# USB-C.net
KiCad netlist of a schematic drawn in Altium Designer
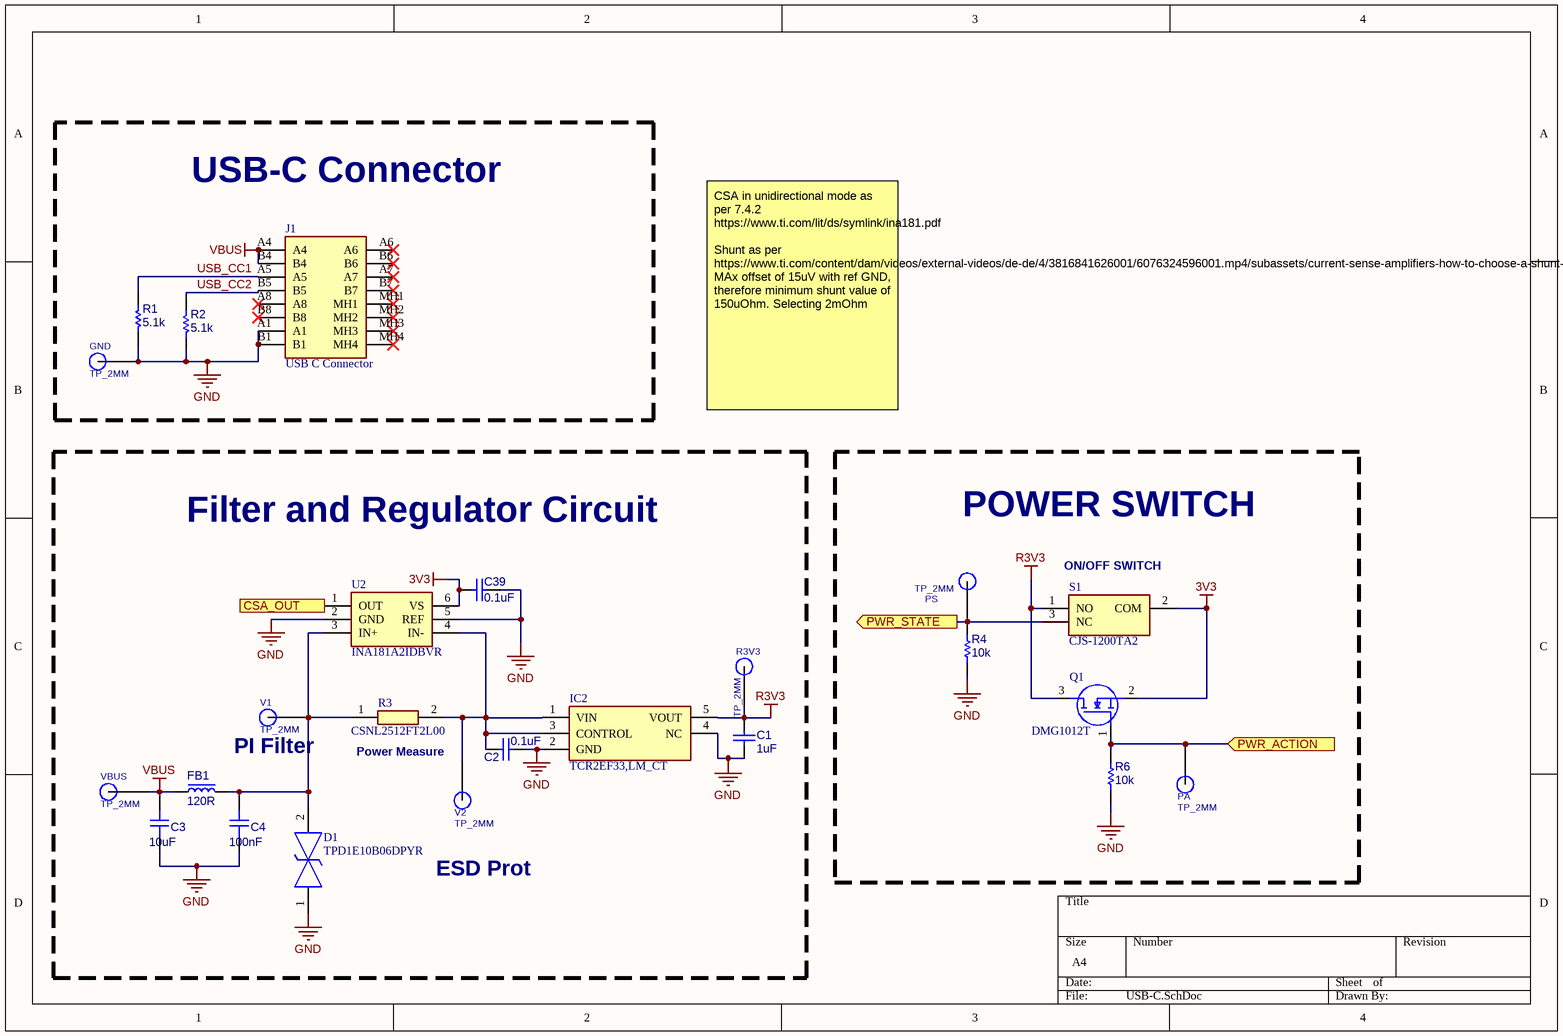
[diagram p0: USB-C.SchDoc]

(export (version "E")
  (design (tool "Eeschema 10.0.6"))
  (components
    (comp (ref "C1")
      (value "1uF")
      (footprint "C0603")
      (description "Capacitor, MLCC, 100nF, 6V3, X5R, 10%, 0603, T=0,8mm")
      (fields
        (field (name "MANUFACTURER PART NUMBER") "CC0603KRX5R5BB104")
        (field (name "MANUFACTURER") "YAGEO")
        (field (name "PROVIDED_BY") "SUBCO")
      )
      (libsource (lib "Perth Aerospace Student Team") (part "CMP-035-000015-1"))
    )
    (comp (ref "C2")
      (value "0.1uF")
      (footprint "C0603")
      (description "Capacitor, MLCC, 100nF, 6V3, X5R, 10%, 0603, T=0,8mm")
      (fields
        (field (name "MANUFACTURER PART NUMBER") "CC0603KRX5R5BB104")
        (field (name "MANUFACTURER") "YAGEO")
        (field (name "PROVIDED_BY") "SUBCO")
      )
      (libsource (lib "Perth Aerospace Student Team") (part "CMP-035-000015-1"))
    )
    (comp (ref "C3")
      (value "CAP_0603_16V")
      (footprint "CAP_0603")
      (description "Capacitor SMD 0603 16V")
      (fields (field (name "SOURCE") "Schematic-Lib-PhilsLab.SchLib"))
      (libsource (lib "Perth Aerospace Student Team") (part "CAP_EL_NP_5MM"))
    )
    (comp (ref "C4")
      (value "CAP_0603_16V")
      (footprint "CAP_0603")
      (description "Capacitor SMD 0603 16V")
      (fields (field (name "SOURCE") "Schematic-Lib-PhilsLab.SchLib"))
      (libsource (lib "Perth Aerospace Student Team") (part "CAP_EL_NP_5MM"))
    )
    (comp (ref "C39")
      (value "0.1uF")
      (footprint "C0603")
      (description "Capacitor, MLCC, 100nF, 6V3, X5R, 10%, 0603, T=0,8mm")
      (fields
        (field (name "MANUFACTURER PART NUMBER") "CC0603KRX5R5BB104")
        (field (name "MANUFACTURER") "YAGEO")
        (field (name "PROVIDED_BY") "SUBCO")
      )
      (libsource (lib "Perth Aerospace Student Team") (part "CMP-035-000015-1"))
    )
    (comp (ref "D1")
      (value "TPD1E10B06DPYR")
      (footprint "TPD1E10B06DPYR")
      (description "TVS Diode (Bi-directional)")
      (fields (field (name "MOUSER PART NUMBER") "595-TPD1E10B06DPYR"))
      (libsource (lib "C2S") (part "TPD1E10B06DPYR"))
    )
    (comp (ref "FB1")
      (value "120R")
      (footprint "FB_0603")
      (description "Ferrite Bead SMD 0603")
      (fields (field (name "SOURCE") "Schematic-Lib-PhilsLab.SchLib"))
      (libsource (lib "Perth Aerospace Student Team") (part "FB_0603"))
    )
    (comp (ref "GND") (value "TP_2MM") (footprint "TESTPOINT 2MM") (libsource (lib "C2S") (part "TP_2MM")))
    (comp (ref "IC2")
      (value "TCR2EF33,LM_CT")
      (footprint "C2Sv0.1:SOT-25")
      (description "Integrated Circuit")
      (fields
        (field (name "MANUFACTURER_PART_NUMBER") "TCR2EF33,LM(CT")
        (field (name "MOUSER PART NUMBER") "757-TCR2EF33LMCT")
      )
      (libsource (lib "C2Sv0.1") (part "TCR2EF33,LM_CT"))
    )
    (comp (ref "J1")
      (value "USB C Connector")
      (footprint "UJ20CHGMSMT2P16TR")
      (description "UJ20-C-H-G-MSMT-2-P16-TR Connector")
      (fields
        (field (name "MOUSER PART NUMBER") "179-UJ20CHGMSMT2P16T")
        (field (name "MANUFACTURER_PART_NUMBER") "UJ20-C-H-G-MSMT-2-P16-TR")
        (field (name "AUTHOR") "Raphael Ho")
      )
      (libsource (lib "Perth Aerospace Student Team") (part "UJ20-C-H-G-MSMT-2-P16-TR"))
    )
    (comp (ref "PA") (value "TP_2MM") (footprint "TESTPOINT 2MM") (libsource (lib "C2S") (part "TP_2MM")))
    (comp (ref "PS") (value "TP_2MM") (footprint "TESTPOINT 2MM") (libsource (lib "C2S") (part "TP_2MM")))
    (comp (ref "Q1")
      (value "DMG1012T")
      (footprint "SOT50P160X90-3N")
      (description "MOSFET (N-Channel)")
      (libsource (lib "C2S") (part "DMG1012T"))
    )
    (comp (ref "R1")
      (value "5.1k")
      (footprint "RESC1608X55X25ML10T15-1")
      (description "Chip Resistor, 10k Ohm, 0.1 W, -55 to 155 degC, 0603 (1608 Metric)")
      (fields
        (field (name "POWER") "100mW")
        (field (name "TOLERANCE") "1%")
        (field (name "CREATED BY") "Micah Randall")
      )
      (libsource (lib "Perth Aerospace Student Team") (part "CMP-009-00006-5"))
    )
    (comp (ref "R2")
      (value "5.1k")
      (footprint "RESC1608X55X25ML10T15-1")
      (description "Chip Resistor, 10k Ohm, 0.1 W, -55 to 155 degC, 0603 (1608 Metric)")
      (fields
        (field (name "POWER") "100mW")
        (field (name "TOLERANCE") "1%")
        (field (name "CREATED BY") "Micah Randall")
      )
      (libsource (lib "Perth Aerospace Student Team") (part "CMP-009-00006-5"))
    )
    (comp (ref "R3")
      (value "CSNL2512FT2L00")
      (footprint "C2Sv0.1:RESC6432X145N")
      (description "Resistor")
      (libsource (lib "*") (part "CSNL2512FT2L00"))
    )
    (comp (ref "R3V3") (value "TP_2MM") (footprint "TESTPOINT 2MM") (libsource (lib "C2S") (part "TP_2MM")))
    (comp (ref "R4")
      (value "10k")
      (footprint "RESC1608X55X25ML10T15-1")
      (description "Chip Resistor, 10k Ohm, 0.1 W, -55 to 155 degC, 0603 (1608 Metric)")
      (fields
        (field (name "POWER") "100mW")
        (field (name "TOLERANCE") "1%")
        (field (name "CREATED BY") "Micah Randall")
      )
      (libsource (lib "Perth Aerospace Student Team") (part "CMP-009-00006-5"))
    )
    (comp (ref "R6")
      (value "10k")
      (footprint "RESC1608X55X25ML10T15-1")
      (description "Chip Resistor, 10k Ohm, 0.1 W, -55 to 155 degC, 0603 (1608 Metric)")
      (fields
        (field (name "POWER") "100mW")
        (field (name "TOLERANCE") "1%")
        (field (name "CREATED BY") "Micah Randall")
      )
      (libsource (lib "Perth Aerospace Student Team") (part "CMP-009-00006-5"))
    )
    (comp (ref "S1")
      (value "CJS-1200TA2")
      (footprint "CJS1200TA2")
      (description "Switch")
      (fields (field (name "MOUSER PART NUMBER") "229-CJS-1200TA2"))
      (libsource (lib "C2S") (part "CJS-1200TA2"))
    )
    (comp (ref "U2")
      (value "INA181A2IDBVR")
      (footprint "C2Sv0.1:SOT95P280X145-6N")
      (description "Undefined or Miscellaneous")
      (fields (field (name "MOUSER PART NUMBER") "595-INA181A2IDBVR"))
      (libsource (lib "*") (part "INA181A2IDBVR"))
    )
    (comp (ref "V1") (value "TP_2MM") (footprint "TESTPOINT 2MM") (libsource (lib "C2S") (part "TP_2MM")))
    (comp (ref "V2") (value "TP_2MM") (footprint "TESTPOINT 2MM") (libsource (lib "C2S") (part "TP_2MM")))
    (comp (ref "VBUS") (value "TP_2MM") (footprint "TESTPOINT 2MM") (libsource (lib "C2S") (part "TP_2MM")))
  )
  (nets
    (net (code "1") (name "/CSA_OUT") (class "Default")
      (node (ref "U2") (pin "1") (pinfunction "OUT_1") (pintype "passive"))
    )
    (net (code "2") (name "/PWR_ACTION") (class "Default")
      (node (ref "PA") (pin "TP") (pinfunction "TP_2MM_TP") (pintype "passive"))
      (node (ref "Q1") (pin "1") (pinfunction "G_1") (pintype "passive"))
      (node (ref "R6") (pin "1") (pinfunction "1_1") (pintype "passive"))
    )
    (net (code "3") (name "/PWR_STATE") (class "Default")
      (node (ref "PS") (pin "TP") (pinfunction "TP_2MM_TP") (pintype "passive"))
      (node (ref "R4") (pin "1") (pinfunction "1_1") (pintype "passive"))
      (node (ref "S1") (pin "3") (pinfunction "NC_3") (pintype "passive"))
    )
    (net (code "4") (name "/USB_CC1") (class "Default")
      (node (ref "J1") (pin "A5") (pinfunction "A5_A5") (pintype "passive"))
      (node (ref "R1") (pin "1") (pinfunction "1_1") (pintype "passive"))
    )
    (net (code "5") (name "/USB_CC2") (class "Default")
      (node (ref "J1") (pin "B5") (pinfunction "B5_B5") (pintype "passive"))
      (node (ref "R2") (pin "1") (pinfunction "1_1") (pintype "passive"))
    )
    (net (code "6") (name "3V3") (class "Default")
      (node (ref "C39") (pin "1") (pinfunction "1_1") (pintype "passive"))
      (node (ref "Q1") (pin "2") (pinfunction "S_2") (pintype "passive"))
      (node (ref "S1") (pin "2") (pinfunction "COM_2") (pintype "passive"))
      (node (ref "U2") (pin "6") (pinfunction "VS_6") (pintype "passive"))
    )
    (net (code "7") (name "GND") (class "Default")
      (node (ref "C1") (pin "2") (pinfunction "2_2") (pintype "passive"))
      (node (ref "C2") (pin "1") (pinfunction "1_1") (pintype "passive"))
      (node (ref "C3") (pin "1") (pinfunction "1_1") (pintype "passive"))
      (node (ref "C39") (pin "2") (pinfunction "2_2") (pintype "passive"))
      (node (ref "C4") (pin "1") (pinfunction "1_1") (pintype "passive"))
      (node (ref "D1") (pin "1") (pinfunction "1_1") (pintype "passive"))
      (node (ref "GND") (pin "TP") (pinfunction "TP_2MM_TP") (pintype "passive"))
      (node (ref "IC2") (pin "2") (pinfunction "GND_2") (pintype "passive"))
      (node (ref "IC2") (pin "4") (pinfunction "NC_4") (pintype "passive"))
      (node (ref "J1") (pin "A1") (pinfunction "A1_A1") (pintype "passive"))
      (node (ref "J1") (pin "B1") (pinfunction "B1_B1") (pintype "passive"))
      (node (ref "R1") (pin "2") (pinfunction "2_2") (pintype "passive"))
      (node (ref "R2") (pin "2") (pinfunction "2_2") (pintype "passive"))
      (node (ref "R4") (pin "2") (pinfunction "2_2") (pintype "passive"))
      (node (ref "R6") (pin "2") (pinfunction "2_2") (pintype "passive"))
      (node (ref "U2") (pin "2") (pinfunction "GND_2") (pintype "passive"))
      (node (ref "U2") (pin "5") (pinfunction "REF_5") (pintype "passive"))
    )
    (net (code "8") (name "Net-(IC2-CONTROL)") (class "Default")
      (node (ref "C2") (pin "2") (pinfunction "2_2") (pintype "passive"))
      (node (ref "IC2") (pin "1") (pinfunction "VIN_1") (pintype "passive"))
      (node (ref "IC2") (pin "3") (pinfunction "CONTROL_3") (pintype "passive"))
      (node (ref "R3") (pin "2") (pinfunction "2_2") (pintype "passive"))
      (node (ref "U2") (pin "4") (pinfunction "IN-_4") (pintype "passive"))
      (node (ref "V2") (pin "TP") (pinfunction "TP_2MM_TP") (pintype "passive"))
    )
    (net (code "9") (name "Net-(U2-IN+)") (class "Default")
      (node (ref "C4") (pin "2") (pinfunction "2_2") (pintype "passive"))
      (node (ref "D1") (pin "2") (pinfunction "2_2") (pintype "passive"))
      (node (ref "FB1") (pin "1") (pinfunction "1_1") (pintype "passive"))
      (node (ref "R3") (pin "1") (pinfunction "1_1") (pintype "passive"))
      (node (ref "U2") (pin "3") (pinfunction "IN+_3") (pintype "passive"))
      (node (ref "V1") (pin "TP") (pinfunction "TP_2MM_TP") (pintype "passive"))
    )
    (net (code "10") (name "R3V3") (class "Default")
      (node (ref "C1") (pin "1") (pinfunction "1_1") (pintype "passive"))
      (node (ref "IC2") (pin "5") (pinfunction "VOUT_5") (pintype "passive"))
      (node (ref "Q1") (pin "3") (pinfunction "D_3") (pintype "passive"))
      (node (ref "R3V3") (pin "TP") (pinfunction "TP_2MM_TP") (pintype "passive"))
      (node (ref "S1") (pin "1") (pinfunction "NO_1") (pintype "passive"))
    )
    (net (code "11") (name "VBUS") (class "Default")
      (node (ref "C3") (pin "2") (pinfunction "2_2") (pintype "passive"))
      (node (ref "FB1") (pin "2") (pinfunction "2_2") (pintype "passive"))
      (node (ref "J1") (pin "A4") (pinfunction "A4_A4") (pintype "passive"))
      (node (ref "J1") (pin "B4") (pinfunction "B4_B4") (pintype "passive"))
      (node (ref "VBUS") (pin "TP") (pinfunction "TP_2MM_TP") (pintype "passive"))
    )
    (net (code "12") (name "unconnected-(J1-PadA6)") (class "Default")
      (node (ref "J1") (pin "A6") (pinfunction "A6_A6") (pintype "passive+no_connect"))
    )
    (net (code "13") (name "unconnected-(J1-PadA7)") (class "Default")
      (node (ref "J1") (pin "A7") (pinfunction "A7_A7") (pintype "passive+no_connect"))
    )
    (net (code "14") (name "unconnected-(J1-PadA8)") (class "Default")
      (node (ref "J1") (pin "A8") (pinfunction "A8_A8") (pintype "passive+no_connect"))
    )
    (net (code "15") (name "unconnected-(J1-PadB6)") (class "Default")
      (node (ref "J1") (pin "B6") (pinfunction "B6_B6") (pintype "passive+no_connect"))
    )
    (net (code "16") (name "unconnected-(J1-PadB7)") (class "Default")
      (node (ref "J1") (pin "B7") (pinfunction "B7_B7") (pintype "passive+no_connect"))
    )
    (net (code "17") (name "unconnected-(J1-PadB8)") (class "Default")
      (node (ref "J1") (pin "B8") (pinfunction "B8_B8") (pintype "passive+no_connect"))
    )
    (net (code "18") (name "unconnected-(J1-PadMH1)") (class "Default")
      (node (ref "J1") (pin "MH1") (pinfunction "MH1_MH1") (pintype "passive+no_connect"))
    )
    (net (code "19") (name "unconnected-(J1-PadMH2)") (class "Default")
      (node (ref "J1") (pin "MH2") (pinfunction "MH2_MH2") (pintype "passive+no_connect"))
    )
    (net (code "20") (name "unconnected-(J1-PadMH3)") (class "Default")
      (node (ref "J1") (pin "MH3") (pinfunction "MH3_MH3") (pintype "passive+no_connect"))
    )
    (net (code "21") (name "unconnected-(J1-PadMH4)") (class "Default")
      (node (ref "J1") (pin "MH4") (pinfunction "MH4_MH4") (pintype "passive+no_connect"))
    )
  )
)
